# Coinmech-Programmer.net
KiCad netlist of a schematic drawn in EAGLE
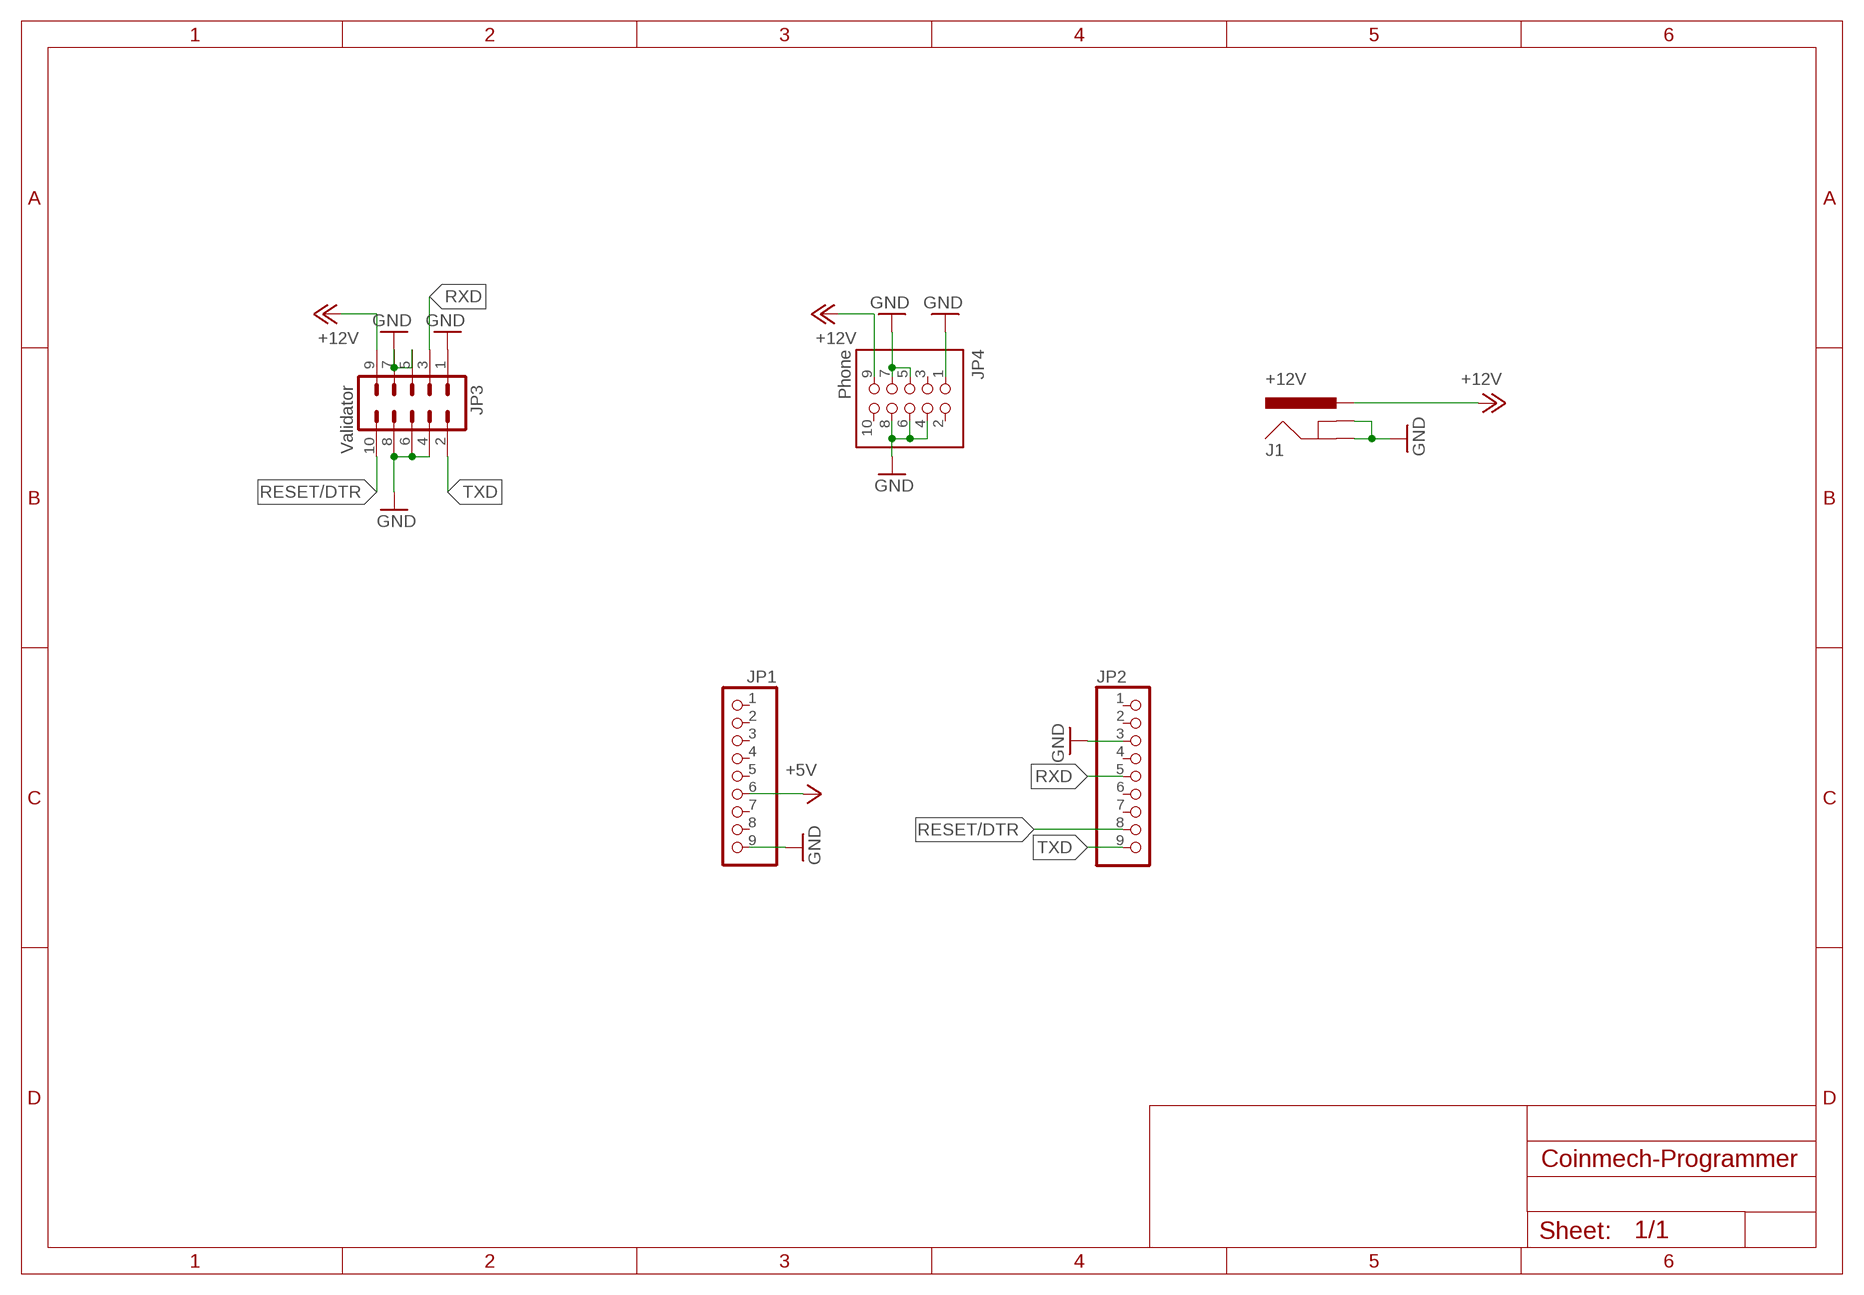
[diagram p0: schematic, sheet 1]

(export (version "E")
  (design (tool "Eeschema 10.0.6"))
  (components
    (comp (ref "J1")
      (value "+12V")
      (footprint "eagle-import:POWER_JACK_PTH")
      (libsource (lib "eagle-import") (part "POWER_JACKPTH"))
    )
    (comp (ref "JP1")
      (value "PINHD-1X9")
      (footprint "eagle-import:1X09")
      (libsource (lib "eagle-import") (part "PINHD-1X9"))
    )
    (comp (ref "JP2")
      (value "PINHD-1X9")
      (footprint "eagle-import:1X09")
      (libsource (lib "eagle-import") (part "PINHD-1X9"))
    )
    (comp (ref "JP3")
      (value "Validator")
      (footprint "eagle-import:2X5-SHROUDED")
      (libsource (lib "eagle-import") (part "M05X2SHD"))
    )
    (comp (ref "JP4")
      (value "Phone")
      (footprint "eagle-import:2X05")
      (libsource (lib "eagle-import") (part "PINHD-2X5"))
    )
  )
  (nets
    (net (code "1") (name "+5V") (class "Default")
      (node (ref "JP1") (pin "6") (pinfunction "6_6") (pintype "passive"))
    )
    (net (code "2") (name "+12V") (class "Default")
      (node (ref "J1") (pin "PWR") (pinfunction "PWR_PWR") (pintype "bidirectional"))
      (node (ref "JP3") (pin "9") (pinfunction "9_9") (pintype "passive"))
      (node (ref "JP4") (pin "9") (pinfunction "9_9") (pintype "passive"))
    )
    (net (code "3") (name "GND") (class "Default")
      (node (ref "J1") (pin "GND") (pinfunction "GND_GND") (pintype "bidirectional"))
      (node (ref "J1") (pin "GNDBREAK") (pinfunction "GNDBREAK_GNDBREAK") (pintype "bidirectional"))
      (node (ref "JP1") (pin "9") (pinfunction "9_9") (pintype "passive"))
      (node (ref "JP2") (pin "3") (pinfunction "3_3") (pintype "passive"))
      (node (ref "JP3") (pin "1") (pinfunction "1_1") (pintype "passive"))
      (node (ref "JP3") (pin "4") (pinfunction "4_4") (pintype "passive"))
      (node (ref "JP3") (pin "5") (pinfunction "5_5") (pintype "passive"))
      (node (ref "JP3") (pin "6") (pinfunction "6_6") (pintype "passive"))
      (node (ref "JP3") (pin "7") (pinfunction "7_7") (pintype "passive"))
      (node (ref "JP3") (pin "8") (pinfunction "8_8") (pintype "passive"))
      (node (ref "JP4") (pin "1") (pinfunction "1_1") (pintype "passive"))
      (node (ref "JP4") (pin "4") (pinfunction "4_4") (pintype "passive"))
      (node (ref "JP4") (pin "5") (pinfunction "5_5") (pintype "passive"))
      (node (ref "JP4") (pin "6") (pinfunction "6_6") (pintype "passive"))
      (node (ref "JP4") (pin "7") (pinfunction "7_7") (pintype "passive"))
      (node (ref "JP4") (pin "8") (pinfunction "8_8") (pintype "passive"))
    )
    (net (code "4") (name "RESET{slash}DTR") (class "Default")
      (node (ref "JP2") (pin "8") (pinfunction "8_8") (pintype "passive"))
      (node (ref "JP3") (pin "10") (pinfunction "10_10") (pintype "passive"))
    )
    (net (code "5") (name "RXD") (class "Default")
      (node (ref "JP2") (pin "5") (pinfunction "5_5") (pintype "passive"))
      (node (ref "JP3") (pin "3") (pinfunction "3_3") (pintype "passive"))
    )
    (net (code "6") (name "TXD") (class "Default")
      (node (ref "JP2") (pin "9") (pinfunction "9_9") (pintype "passive"))
      (node (ref "JP3") (pin "2") (pinfunction "2_2") (pintype "passive"))
    )
    (net (code "7") (name "unconnected-(JP1-Pad1)") (class "Default")
      (node (ref "JP1") (pin "1") (pinfunction "1_1") (pintype "passive"))
    )
    (net (code "8") (name "unconnected-(JP1-Pad2)") (class "Default")
      (node (ref "JP1") (pin "2") (pinfunction "2_2") (pintype "passive"))
    )
    (net (code "9") (name "unconnected-(JP1-Pad3)") (class "Default")
      (node (ref "JP1") (pin "3") (pinfunction "3_3") (pintype "passive"))
    )
    (net (code "10") (name "unconnected-(JP1-Pad4)") (class "Default")
      (node (ref "JP1") (pin "4") (pinfunction "4_4") (pintype "passive"))
    )
    (net (code "11") (name "unconnected-(JP1-Pad5)") (class "Default")
      (node (ref "JP1") (pin "5") (pinfunction "5_5") (pintype "passive"))
    )
    (net (code "12") (name "unconnected-(JP1-Pad7)") (class "Default")
      (node (ref "JP1") (pin "7") (pinfunction "7_7") (pintype "passive"))
    )
    (net (code "13") (name "unconnected-(JP1-Pad8)") (class "Default")
      (node (ref "JP1") (pin "8") (pinfunction "8_8") (pintype "passive"))
    )
    (net (code "14") (name "unconnected-(JP2-Pad1)") (class "Default")
      (node (ref "JP2") (pin "1") (pinfunction "1_1") (pintype "passive"))
    )
    (net (code "15") (name "unconnected-(JP2-Pad2)") (class "Default")
      (node (ref "JP2") (pin "2") (pinfunction "2_2") (pintype "passive"))
    )
    (net (code "16") (name "unconnected-(JP2-Pad4)") (class "Default")
      (node (ref "JP2") (pin "4") (pinfunction "4_4") (pintype "passive"))
    )
    (net (code "17") (name "unconnected-(JP2-Pad6)") (class "Default")
      (node (ref "JP2") (pin "6") (pinfunction "6_6") (pintype "passive"))
    )
    (net (code "18") (name "unconnected-(JP2-Pad7)") (class "Default")
      (node (ref "JP2") (pin "7") (pinfunction "7_7") (pintype "passive"))
    )
    (net (code "19") (name "unconnected-(JP4-Pad2)") (class "Default")
      (node (ref "JP4") (pin "2") (pinfunction "2_2") (pintype "passive"))
    )
    (net (code "20") (name "unconnected-(JP4-Pad3)") (class "Default")
      (node (ref "JP4") (pin "3") (pinfunction "3_3") (pintype "passive"))
    )
    (net (code "21") (name "unconnected-(JP4-Pad10)") (class "Default")
      (node (ref "JP4") (pin "10") (pinfunction "10_10") (pintype "passive"))
    )
  )
)
